# pandemic_proto_v0001.net
KiCad netlist of a schematic drawn in EAGLE
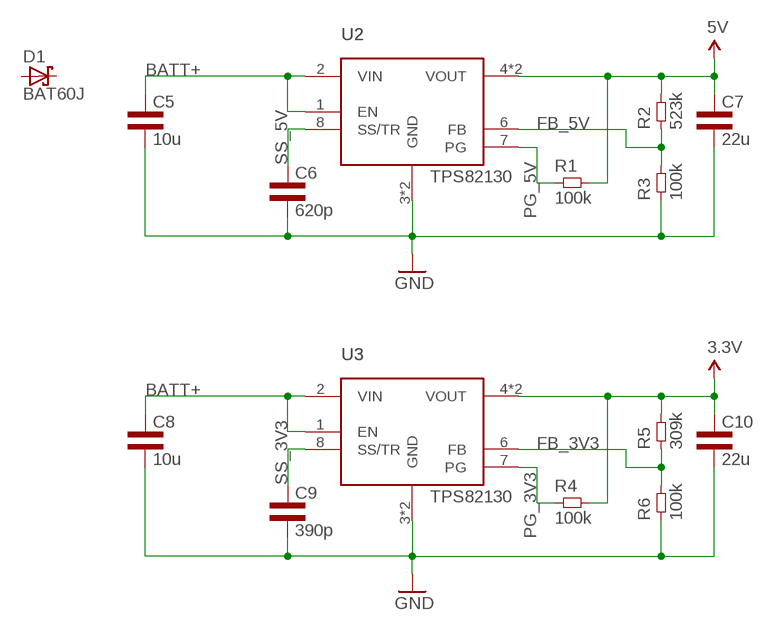
[diagram p0: schematic, sheet 1]
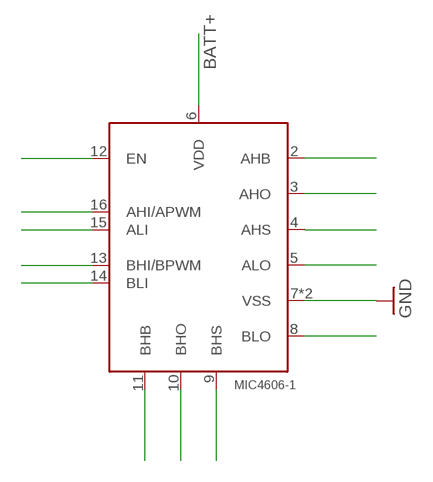
[diagram p1: schematic, sheet 2]
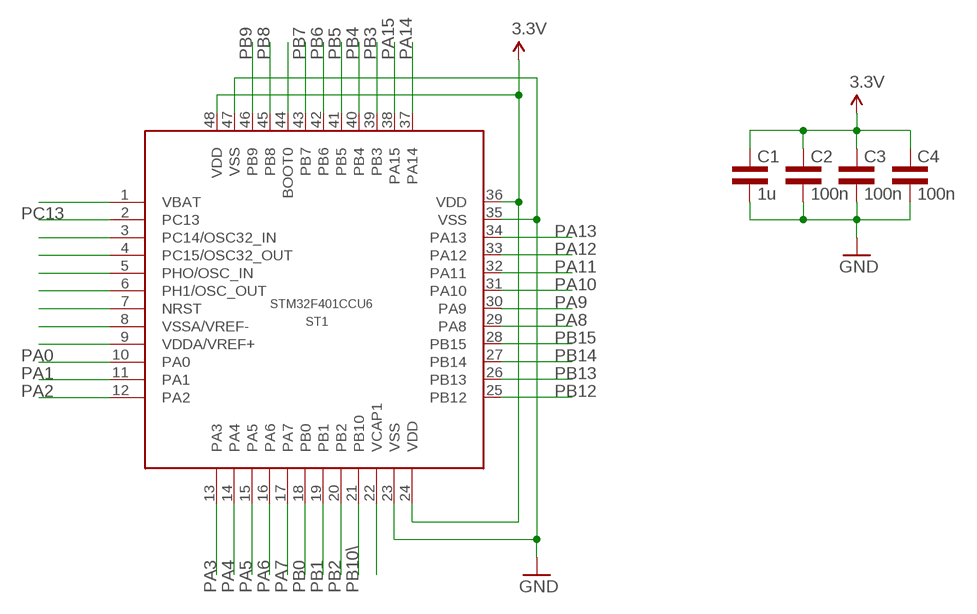
[diagram p2: schematic, sheet 3]
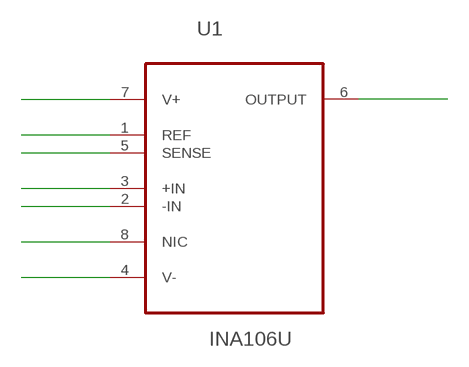
[diagram p3: schematic, sheet 4]

(export (version "E")
  (design (tool "Eeschema 10.0.6"))
  (components
    (comp (ref "C5")
      (value "10u")
      (footprint "eagle-import:1206L3")
      (libsource (lib "eagle-import") (part "CAP1206L3"))
    )
    (comp (ref "C6")
      (value "620p")
      (footprint "eagle-import:0402L3")
      (libsource (lib "eagle-import") (part "CAP0402L3"))
    )
    (comp (ref "C7")
      (value "22u")
      (footprint "eagle-import:0805L3")
      (libsource (lib "eagle-import") (part "CAP0805L3"))
    )
    (comp (ref "C8")
      (value "10u")
      (footprint "eagle-import:1206L3")
      (libsource (lib "eagle-import") (part "CAP1206L3"))
    )
    (comp (ref "C9")
      (value "390p")
      (footprint "eagle-import:0402L3")
      (libsource (lib "eagle-import") (part "CAP0402L3"))
    )
    (comp (ref "C10")
      (value "22u")
      (footprint "eagle-import:0805L3")
      (libsource (lib "eagle-import") (part "CAP0805L3"))
    )
    (comp (ref "D1")
      (value "BAT60J")
      (footprint "eagle-import:SOD323_ST")
      (libsource (lib "eagle-import") (part "BAT60J"))
    )
    (comp (ref "R1")
      (value "100k")
      (footprint "eagle-import:0402L3")
      (libsource (lib "eagle-import") (part "RES0402L3"))
    )
    (comp (ref "R2")
      (value "523k")
      (footprint "eagle-import:0402L3")
      (libsource (lib "eagle-import") (part "RES0402L3"))
    )
    (comp (ref "R3")
      (value "100k")
      (footprint "eagle-import:0805L3")
      (libsource (lib "eagle-import") (part "RES0805L3"))
    )
    (comp (ref "R4")
      (value "100k")
      (footprint "eagle-import:0402L3")
      (libsource (lib "eagle-import") (part "RES0402L3"))
    )
    (comp (ref "R5")
      (value "309k")
      (footprint "eagle-import:0402L3")
      (libsource (lib "eagle-import") (part "RES0402L3"))
    )
    (comp (ref "R6")
      (value "100k")
      (footprint "eagle-import:0805L3")
      (libsource (lib "eagle-import") (part "RES0805L3"))
    )
    (comp (ref "U2")
      (value "TPS82130")
      (footprint "eagle-import:SIL0008C")
      (libsource (lib "eagle-import") (part "TPS82130"))
    )
    (comp (ref "U3")
      (value "TPS82130")
      (footprint "eagle-import:SIL0008C")
      (libsource (lib "eagle-import") (part "TPS82130"))
    )
    (comp (ref "C1")
      (value "1u")
      (footprint "eagle-import:0805L3")
      (libsource (lib "eagle-import") (part "CAP0805L3"))
    )
    (comp (ref "C2")
      (value "100n")
      (footprint "eagle-import:0402L3")
      (libsource (lib "eagle-import") (part "CAP0402L3"))
    )
    (comp (ref "C3")
      (value "100n")
      (footprint "eagle-import:0402L3")
      (libsource (lib "eagle-import") (part "CAP0402L3"))
    )
    (comp (ref "C4")
      (value "100n")
      (footprint "eagle-import:0402L3")
      (libsource (lib "eagle-import") (part "CAP0402L3"))
    )
    (comp (ref "ST1")
      (value "STM32F401CCU6")
      (footprint "eagle-import:UFQFPN48")
      (libsource (lib "eagle-import") (part "STM32F401CCU6"))
    )
    (comp (ref "U1")
      (value "INA106U")
      (footprint "eagle-import:SOIC127P600X175-8N")
      (libsource (lib "eagle-import") (part "INA106U"))
    )
    (comp (ref "MD1")
      (value "MIC4606-1")
      (footprint "eagle-import:QFN44-16LD-PL-2")
      (libsource (lib "eagle-import") (part "MIC4606-1"))
    )
  )
  (nets
    (net (code "1") (name "3.3V") (class "Default")
      (node (ref "C1") (pin "1") (pinfunction "1_1") (pintype "bidirectional"))
      (node (ref "C10") (pin "1") (pinfunction "1_1") (pintype "bidirectional"))
      (node (ref "C2") (pin "P$1") (pinfunction "1_P$1") (pintype "bidirectional"))
      (node (ref "C3") (pin "P$1") (pinfunction "1_P$1") (pintype "bidirectional"))
      (node (ref "C4") (pin "P$1") (pinfunction "1_P$1") (pintype "bidirectional"))
      (node (ref "R4") (pin "P$2") (pinfunction "2_P$2") (pintype "bidirectional"))
      (node (ref "R5") (pin "P$2") (pinfunction "2_P$2") (pintype "bidirectional"))
      (node (ref "ST1") (pin "24") (pinfunction "VDD_24") (pintype "bidirectional"))
      (node (ref "ST1") (pin "36") (pinfunction "VDD_36") (pintype "bidirectional"))
      (node (ref "ST1") (pin "48") (pinfunction "VDD_48") (pintype "bidirectional"))
      (node (ref "U3") (pin "4") (pinfunction "VOUT_4") (pintype "bidirectional"))
      (node (ref "U3") (pin "5") (pinfunction "VOUT_5") (pintype "bidirectional"))
    )
    (net (code "2") (name "5V") (class "Default")
      (node (ref "C7") (pin "1") (pinfunction "1_1") (pintype "bidirectional"))
      (node (ref "R1") (pin "P$2") (pinfunction "2_P$2") (pintype "bidirectional"))
      (node (ref "R2") (pin "P$2") (pinfunction "2_P$2") (pintype "bidirectional"))
      (node (ref "U2") (pin "4") (pinfunction "VOUT_4") (pintype "bidirectional"))
      (node (ref "U2") (pin "5") (pinfunction "VOUT_5") (pintype "bidirectional"))
    )
    (net (code "3") (name "BATT+") (class "Default")
      (node (ref "C5") (pin "1") (pinfunction "1_1") (pintype "bidirectional"))
      (node (ref "C8") (pin "1") (pinfunction "1_1") (pintype "bidirectional"))
      (node (ref "MD1") (pin "6") (pinfunction "VDD_6") (pintype "bidirectional"))
      (node (ref "U2") (pin "1") (pinfunction "EN_1") (pintype "bidirectional"))
      (node (ref "U2") (pin "2") (pinfunction "VIN_2") (pintype "bidirectional"))
      (node (ref "U3") (pin "1") (pinfunction "EN_1") (pintype "bidirectional"))
      (node (ref "U3") (pin "2") (pinfunction "VIN_2") (pintype "bidirectional"))
    )
    (net (code "4") (name "FB_3V3") (class "Default")
      (node (ref "R5") (pin "P$1") (pinfunction "1_P$1") (pintype "bidirectional"))
      (node (ref "R6") (pin "2") (pinfunction "2_2") (pintype "bidirectional"))
      (node (ref "U3") (pin "6") (pinfunction "FB_6") (pintype "bidirectional"))
    )
    (net (code "5") (name "FB_5V") (class "Default")
      (node (ref "R2") (pin "P$1") (pinfunction "1_P$1") (pintype "bidirectional"))
      (node (ref "R3") (pin "2") (pinfunction "2_2") (pintype "bidirectional"))
      (node (ref "U2") (pin "6") (pinfunction "FB_6") (pintype "bidirectional"))
    )
    (net (code "6") (name "GND") (class "Default")
      (node (ref "C1") (pin "2") (pinfunction "2_2") (pintype "bidirectional"))
      (node (ref "C10") (pin "2") (pinfunction "2_2") (pintype "bidirectional"))
      (node (ref "C2") (pin "P$2") (pinfunction "2_P$2") (pintype "bidirectional"))
      (node (ref "C3") (pin "P$2") (pinfunction "2_P$2") (pintype "bidirectional"))
      (node (ref "C4") (pin "P$2") (pinfunction "2_P$2") (pintype "bidirectional"))
      (node (ref "C5") (pin "2") (pinfunction "2_2") (pintype "bidirectional"))
      (node (ref "C6") (pin "P$2") (pinfunction "2_P$2") (pintype "bidirectional"))
      (node (ref "C7") (pin "2") (pinfunction "2_2") (pintype "bidirectional"))
      (node (ref "C8") (pin "2") (pinfunction "2_2") (pintype "bidirectional"))
      (node (ref "C9") (pin "P$2") (pinfunction "2_P$2") (pintype "bidirectional"))
      (node (ref "MD1") (pin "7") (pinfunction "VSS_7") (pintype "bidirectional"))
      (node (ref "MD1") (pin "TP") (pinfunction "VSS_TP") (pintype "bidirectional"))
      (node (ref "R3") (pin "1") (pinfunction "1_1") (pintype "bidirectional"))
      (node (ref "R6") (pin "1") (pinfunction "1_1") (pintype "bidirectional"))
      (node (ref "ST1") (pin "23") (pinfunction "VSS_23") (pintype "bidirectional"))
      (node (ref "ST1") (pin "35") (pinfunction "VSS_35") (pintype "bidirectional"))
      (node (ref "ST1") (pin "47") (pinfunction "VSS_47") (pintype "bidirectional"))
      (node (ref "U2") (pin "3") (pinfunction "GND_3") (pintype "bidirectional"))
      (node (ref "U2") (pin "TP") (pinfunction "GND_TP") (pintype "bidirectional"))
      (node (ref "U3") (pin "3") (pinfunction "GND_3") (pintype "bidirectional"))
      (node (ref "U3") (pin "TP") (pinfunction "GND_TP") (pintype "bidirectional"))
    )
    (net (code "7") (name "PA0") (class "Default")
      (node (ref "ST1") (pin "10") (pinfunction "PA0_10") (pintype "bidirectional"))
    )
    (net (code "8") (name "PA1") (class "Default")
      (node (ref "ST1") (pin "11") (pinfunction "PA1_11") (pintype "bidirectional"))
    )
    (net (code "9") (name "PA2") (class "Default")
      (node (ref "ST1") (pin "12") (pinfunction "PA2_12") (pintype "bidirectional"))
    )
    (net (code "10") (name "PA3") (class "Default")
      (node (ref "ST1") (pin "13") (pinfunction "PA3_13") (pintype "bidirectional"))
    )
    (net (code "11") (name "PA4") (class "Default")
      (node (ref "ST1") (pin "14") (pinfunction "PA4_14") (pintype "bidirectional"))
    )
    (net (code "12") (name "PA5") (class "Default")
      (node (ref "ST1") (pin "15") (pinfunction "PA5_15") (pintype "bidirectional"))
    )
    (net (code "13") (name "PA6") (class "Default")
      (node (ref "ST1") (pin "16") (pinfunction "PA6_16") (pintype "bidirectional"))
    )
    (net (code "14") (name "PA7") (class "Default")
      (node (ref "ST1") (pin "17") (pinfunction "PA7_17") (pintype "bidirectional"))
    )
    (net (code "15") (name "PA8") (class "Default")
      (node (ref "ST1") (pin "29") (pinfunction "PA8_29") (pintype "bidirectional"))
    )
    (net (code "16") (name "PA9") (class "Default")
      (node (ref "ST1") (pin "30") (pinfunction "PA9_30") (pintype "bidirectional"))
    )
    (net (code "17") (name "PA10") (class "Default")
      (node (ref "ST1") (pin "31") (pinfunction "PA10_31") (pintype "bidirectional"))
    )
    (net (code "18") (name "PA11") (class "Default")
      (node (ref "ST1") (pin "32") (pinfunction "PA11_32") (pintype "bidirectional"))
    )
    (net (code "19") (name "PA12") (class "Default")
      (node (ref "ST1") (pin "33") (pinfunction "PA12_33") (pintype "bidirectional"))
    )
    (net (code "20") (name "PA13") (class "Default")
      (node (ref "ST1") (pin "34") (pinfunction "PA13_34") (pintype "bidirectional"))
    )
    (net (code "21") (name "PA14") (class "Default")
      (node (ref "ST1") (pin "37") (pinfunction "PA14_37") (pintype "bidirectional"))
    )
    (net (code "22") (name "PA15") (class "Default")
      (node (ref "ST1") (pin "38") (pinfunction "PA15_38") (pintype "bidirectional"))
    )
    (net (code "23") (name "PB0") (class "Default")
      (node (ref "ST1") (pin "18") (pinfunction "PB0_18") (pintype "bidirectional"))
    )
    (net (code "24") (name "PB1") (class "Default")
      (node (ref "ST1") (pin "19") (pinfunction "PB1_19") (pintype "bidirectional"))
    )
    (net (code "25") (name "PB2") (class "Default")
      (node (ref "ST1") (pin "20") (pinfunction "PB2_20") (pintype "bidirectional"))
    )
    (net (code "26") (name "PB3") (class "Default")
      (node (ref "ST1") (pin "39") (pinfunction "PB3_39") (pintype "bidirectional"))
    )
    (net (code "27") (name "PB4") (class "Default")
      (node (ref "ST1") (pin "40") (pinfunction "PB4_40") (pintype "bidirectional"))
    )
    (net (code "28") (name "PB5") (class "Default")
      (node (ref "ST1") (pin "41") (pinfunction "PB5_41") (pintype "bidirectional"))
    )
    (net (code "29") (name "PB6") (class "Default")
      (node (ref "ST1") (pin "42") (pinfunction "PB6_42") (pintype "bidirectional"))
    )
    (net (code "30") (name "PB7") (class "Default")
      (node (ref "ST1") (pin "43") (pinfunction "PB7_43") (pintype "bidirectional"))
    )
    (net (code "31") (name "PB8") (class "Default")
      (node (ref "ST1") (pin "45") (pinfunction "PB8_45") (pintype "bidirectional"))
    )
    (net (code "32") (name "PB9") (class "Default")
      (node (ref "ST1") (pin "46") (pinfunction "PB9_46") (pintype "bidirectional"))
    )
    (net (code "33") (name "PB10\\") (class "Default")
      (node (ref "ST1") (pin "21") (pinfunction "PB10_21") (pintype "bidirectional"))
    )
    (net (code "34") (name "PB12") (class "Default")
      (node (ref "ST1") (pin "25") (pinfunction "PB12_25") (pintype "bidirectional"))
    )
    (net (code "35") (name "PB13") (class "Default")
      (node (ref "ST1") (pin "26") (pinfunction "PB13_26") (pintype "bidirectional"))
    )
    (net (code "36") (name "PB14") (class "Default")
      (node (ref "ST1") (pin "27") (pinfunction "PB14_27") (pintype "bidirectional"))
    )
    (net (code "37") (name "PB15") (class "Default")
      (node (ref "ST1") (pin "28") (pinfunction "PB15_28") (pintype "bidirectional"))
    )
    (net (code "38") (name "PC13") (class "Default")
      (node (ref "ST1") (pin "2") (pinfunction "PC13_2") (pintype "bidirectional"))
    )
    (net (code "39") (name "PG_3V3") (class "Default")
      (node (ref "R4") (pin "P$1") (pinfunction "1_P$1") (pintype "bidirectional"))
      (node (ref "U3") (pin "7") (pinfunction "PG_7") (pintype "bidirectional"))
    )
    (net (code "40") (name "PG_5V") (class "Default")
      (node (ref "R1") (pin "P$1") (pinfunction "1_P$1") (pintype "bidirectional"))
      (node (ref "U2") (pin "7") (pinfunction "PG_7") (pintype "bidirectional"))
    )
    (net (code "41") (name "SS_3V3") (class "Default")
      (node (ref "C9") (pin "P$1") (pinfunction "1_P$1") (pintype "bidirectional"))
      (node (ref "U3") (pin "8") (pinfunction "SS/TR_8") (pintype "bidirectional"))
    )
    (net (code "42") (name "SS_5V") (class "Default")
      (node (ref "C6") (pin "P$1") (pinfunction "1_P$1") (pintype "bidirectional"))
      (node (ref "U2") (pin "8") (pinfunction "SS/TR_8") (pintype "bidirectional"))
    )
    (net (code "43") (name "unconnected-(D1-PadA)") (class "Default")
      (node (ref "D1") (pin "A") (pinfunction "A_A") (pintype "passive"))
    )
    (net (code "44") (name "unconnected-(D1-PadC)") (class "Default")
      (node (ref "D1") (pin "C") (pinfunction "C_C") (pintype "passive"))
    )
    (net (code "45") (name "unconnected-(MD1-AHB-Pad2)") (class "Default")
      (node (ref "MD1") (pin "2") (pinfunction "AHB_2") (pintype "bidirectional"))
    )
    (net (code "46") (name "unconnected-(MD1-AHI{slash}APWM-Pad16)") (class "Default")
      (node (ref "MD1") (pin "16") (pinfunction "AHI/APWM_16") (pintype "bidirectional"))
    )
    (net (code "47") (name "unconnected-(MD1-AHO-Pad3)") (class "Default")
      (node (ref "MD1") (pin "3") (pinfunction "AHO_3") (pintype "bidirectional"))
    )
    (net (code "48") (name "unconnected-(MD1-AHS-Pad4)") (class "Default")
      (node (ref "MD1") (pin "4") (pinfunction "AHS_4") (pintype "bidirectional"))
    )
    (net (code "49") (name "unconnected-(MD1-ALI-Pad15)") (class "Default")
      (node (ref "MD1") (pin "15") (pinfunction "ALI_15") (pintype "bidirectional"))
    )
    (net (code "50") (name "unconnected-(MD1-ALO-Pad5)") (class "Default")
      (node (ref "MD1") (pin "5") (pinfunction "ALO_5") (pintype "bidirectional"))
    )
    (net (code "51") (name "unconnected-(MD1-BHB-Pad11)") (class "Default")
      (node (ref "MD1") (pin "11") (pinfunction "BHB_11") (pintype "bidirectional"))
    )
    (net (code "52") (name "unconnected-(MD1-BHI{slash}BPWM-Pad13)") (class "Default")
      (node (ref "MD1") (pin "13") (pinfunction "BHI/BPWM_13") (pintype "bidirectional"))
    )
    (net (code "53") (name "unconnected-(MD1-BHO-Pad10)") (class "Default")
      (node (ref "MD1") (pin "10") (pinfunction "BHO_10") (pintype "bidirectional"))
    )
    (net (code "54") (name "unconnected-(MD1-BHS-Pad9)") (class "Default")
      (node (ref "MD1") (pin "9") (pinfunction "BHS_9") (pintype "bidirectional"))
    )
    (net (code "55") (name "unconnected-(MD1-BLI-Pad14)") (class "Default")
      (node (ref "MD1") (pin "14") (pinfunction "BLI_14") (pintype "bidirectional"))
    )
    (net (code "56") (name "unconnected-(MD1-BLO-Pad8)") (class "Default")
      (node (ref "MD1") (pin "8") (pinfunction "BLO_8") (pintype "bidirectional"))
    )
    (net (code "57") (name "unconnected-(MD1-EN-Pad12)") (class "Default")
      (node (ref "MD1") (pin "12") (pinfunction "EN_12") (pintype "bidirectional"))
    )
    (net (code "58") (name "unconnected-(ST1-BOOT0-Pad44)") (class "Default")
      (node (ref "ST1") (pin "44") (pinfunction "BOOT0_44") (pintype "bidirectional"))
    )
    (net (code "59") (name "unconnected-(ST1-NRST-Pad7)") (class "Default")
      (node (ref "ST1") (pin "7") (pinfunction "NRST_7") (pintype "bidirectional"))
    )
    (net (code "60") (name "unconnected-(ST1-PC14{slash}OSC32_IN-Pad3)") (class "Default")
      (node (ref "ST1") (pin "3") (pinfunction "PC14/OSC32_IN_3") (pintype "bidirectional"))
    )
    (net (code "61") (name "unconnected-(ST1-PC15{slash}OSC32_OUT-Pad4)") (class "Default")
      (node (ref "ST1") (pin "4") (pinfunction "PC15/OSC32_OUT_4") (pintype "bidirectional"))
    )
    (net (code "62") (name "unconnected-(ST1-PH1{slash}OSC_OUT-Pad6)") (class "Default")
      (node (ref "ST1") (pin "6") (pinfunction "PH1/OSC_OUT_6") (pintype "bidirectional"))
    )
    (net (code "63") (name "unconnected-(ST1-PHO{slash}OSC_IN-Pad5)") (class "Default")
      (node (ref "ST1") (pin "5") (pinfunction "PHO/OSC_IN_5") (pintype "bidirectional"))
    )
    (net (code "64") (name "unconnected-(ST1-VBAT-Pad1)") (class "Default")
      (node (ref "ST1") (pin "1") (pinfunction "VBAT_1") (pintype "bidirectional"))
    )
    (net (code "65") (name "unconnected-(ST1-VCAP1-Pad22)") (class "Default")
      (node (ref "ST1") (pin "22") (pinfunction "VCAP1_22") (pintype "bidirectional"))
    )
    (net (code "66") (name "unconnected-(ST1-VDDA{slash}VREF+-Pad9)") (class "Default")
      (node (ref "ST1") (pin "9") (pinfunction "VDDA/VREF+_9") (pintype "bidirectional"))
    )
    (net (code "67") (name "unconnected-(ST1-VSSA{slash}VREF--Pad8)") (class "Default")
      (node (ref "ST1") (pin "8") (pinfunction "VSSA/VREF-_8") (pintype "bidirectional"))
    )
    (net (code "68") (name "unconnected-(U1-+IN-Pad3)") (class "Default")
      (node (ref "U1") (pin "3") (pinfunction "+IN_3") (pintype "input"))
    )
    (net (code "69") (name "unconnected-(U1--IN-Pad2)") (class "Default")
      (node (ref "U1") (pin "2") (pinfunction "-IN_2") (pintype "input"))
    )
    (net (code "70") (name "unconnected-(U1-NIC-Pad8)") (class "Default")
      (node (ref "U1") (pin "8") (pinfunction "NIC_8") (pintype "no_connect"))
    )
    (net (code "71") (name "unconnected-(U1-OUTPUT-Pad6)") (class "Default")
      (node (ref "U1") (pin "6") (pinfunction "OUTPUT_6") (pintype "output"))
    )
    (net (code "72") (name "unconnected-(U1-REF-Pad1)") (class "Default")
      (node (ref "U1") (pin "1") (pinfunction "REF_1") (pintype "input"))
    )
    (net (code "73") (name "unconnected-(U1-SENSE-Pad5)") (class "Default")
      (node (ref "U1") (pin "5") (pinfunction "SENSE_5") (pintype "input"))
    )
    (net (code "74") (name "unconnected-(U1-V+-Pad7)") (class "Default")
      (node (ref "U1") (pin "7") (pinfunction "V+_7") (pintype "power_in"))
    )
    (net (code "75") (name "unconnected-(U1-V--Pad4)") (class "Default")
      (node (ref "U1") (pin "4") (pinfunction "V-_4") (pintype "power_in"))
    )
  )
)
